# Fish_Feeder_Schematic_Version_2.net
KiCad netlist of a schematic drawn in Altium Designer
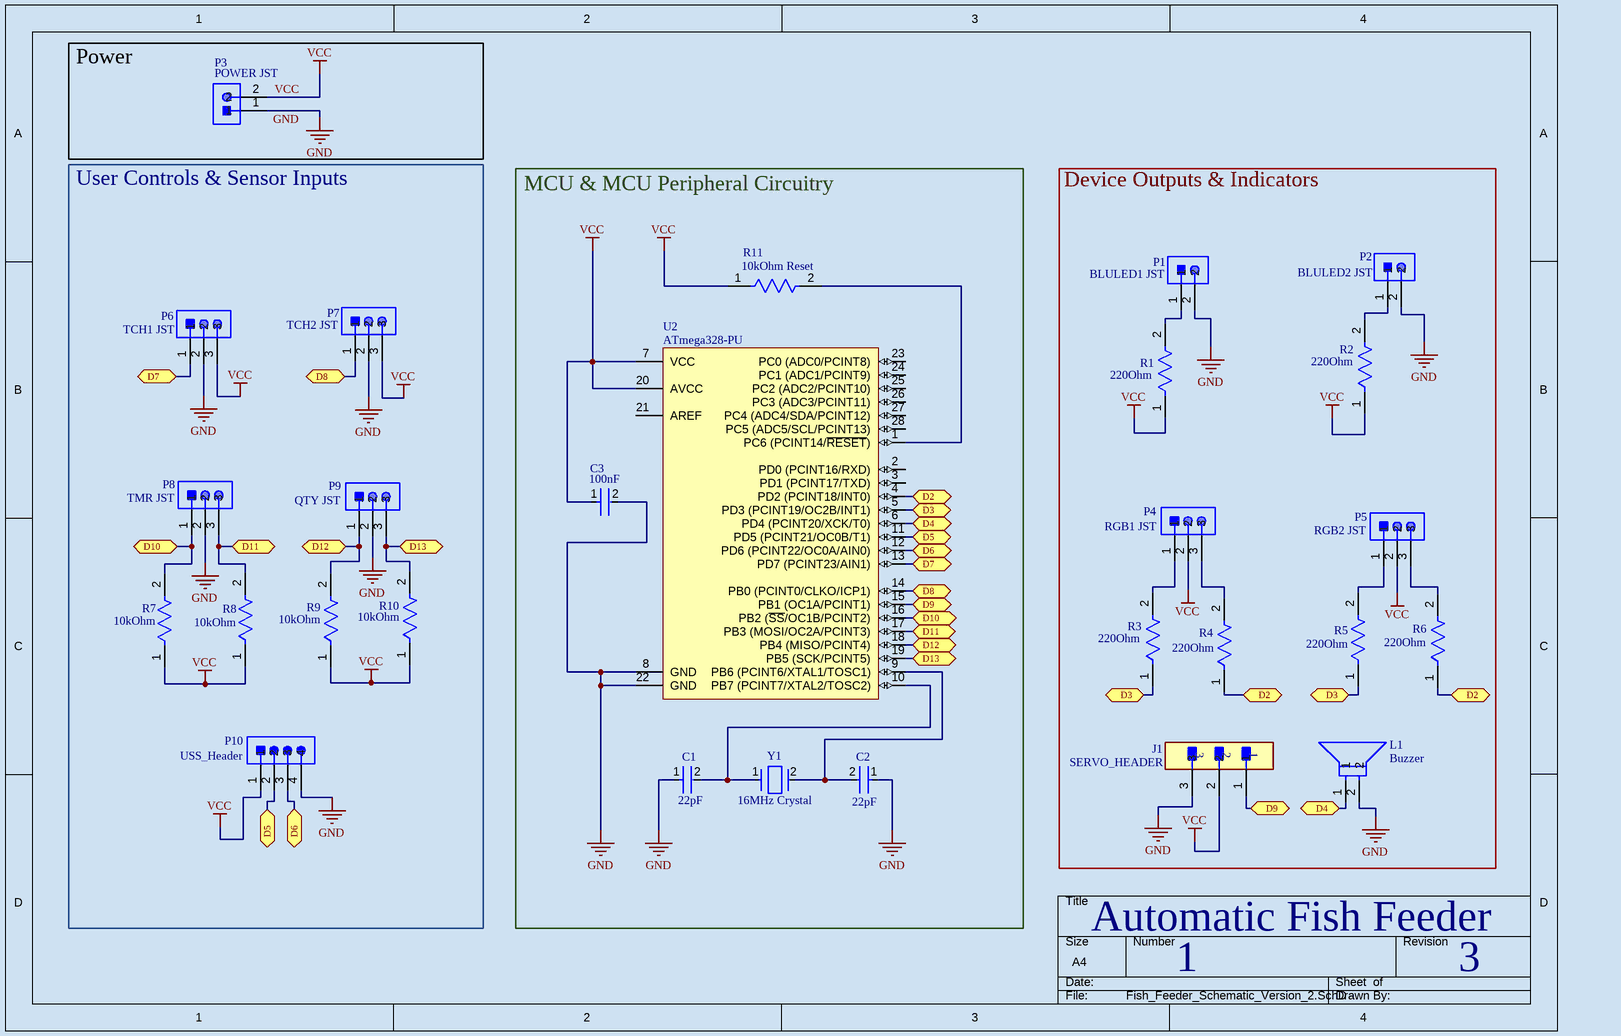
[diagram p0: Fish_Feeder_Schematic_Version_2.SchDoc]

(export (version "E")
  (design (tool "Eeschema 10.0.6"))
  (components
    (comp (ref "C1")
      (value "22pF")
      (footprint "FP-VY1470-MFG")
      (description "CAP CER 2200PF 760VAC Y5U RADIAL")
      (fields (field (name "VOLTAGE") "500V") (field (name "TOLERANCE") "20%"))
      (libsource (lib "Altium Content Vault") (part "11868f565c42a9108669ba33697ecf6"))
    )
    (comp (ref "C2")
      (value "22pF")
      (footprint "FP-VY1470-MFG")
      (description "CAP CER 2200PF 760VAC Y5U RADIAL")
      (fields (field (name "VOLTAGE") "500V") (field (name "TOLERANCE") "20%"))
      (libsource (lib "Altium Content Vault") (part "11868f565c42a9108669ba33697ecf6"))
    )
    (comp (ref "C3")
      (value "100nF")
      (footprint "FP-VY1470-MFG")
      (description "CAP CER 2200PF 760VAC Y5U RADIAL")
      (fields (field (name "VOLTAGE") "500V") (field (name "TOLERANCE") "20%"))
      (libsource (lib "Altium Content Vault") (part "11868f565c42a9108669ba33697ecf6"))
    )
    (comp (ref "J1")
      (value "SERVO_HEADER")
      (footprint "FP-87224-3-MFG")
      (description "CONN HEADER VERT 3POS 2.54MM")
      (libsource (lib "Altium Content Vault") (part "0d3f023dd272f625e17a2be33dea85f"))
    )
    (comp (ref "L1")
      (value "Buzzer")
      (footprint "FP-PS1440P02BT-MFG")
      (description "AUDIO PIEZO TRANSDUCER 30V TH")
      (libsource (lib "Altium Content Vault") (part "5f581d31613f872430949aa526fd155"))
    )
    (comp (ref "P1")
      (value "BLULED1 JST")
      (footprint "JST-S2B-PH-K-S_V")
      (fields (field (name "TOLERANCE") "20%"))
      (libsource (lib "Altium Content Vault") (part "CN-1P-M-R2"))
    )
    (comp (ref "P2")
      (value "BLULED2 JST")
      (footprint "JST-S2B-PH-K-S_V")
      (fields (field (name "TOLERANCE") "20%"))
      (libsource (lib "Altium Content Vault") (part "CN-1P-M-R2"))
    )
    (comp (ref "P3")
      (value "POWER JST")
      (footprint "JST-S2B-PH-K-S_V")
      (fields (field (name "TOLERANCE") "20%"))
      (libsource (lib "") (part "CN-1P-M-R2_1"))
    )
    (comp (ref "P4")
      (value "RGB1 JST")
      (footprint "JST-B3B-PH-K-S-3_V")
      (fields (field (name "MANUFACTURER") "JST"))
      (libsource (lib "Altium Content Vault") (part "CN-1P-M-R3"))
    )
    (comp (ref "P5")
      (value "RGB2 JST")
      (footprint "JST-B3B-PH-K-S-3_V")
      (fields (field (name "MANUFACTURER") "JST"))
      (libsource (lib "Altium Content Vault") (part "CN-1P-M-R3"))
    )
    (comp (ref "P6")
      (value "TCH1 JST")
      (footprint "JST-B3B-PH-K-S-3_V")
      (fields (field (name "MANUFACTURER") "JST"))
      (libsource (lib "Altium Content Vault") (part "CN-1P-M-R3"))
    )
    (comp (ref "P7")
      (value "TCH2 JST")
      (footprint "JST-B3B-PH-K-S-3_V")
      (fields (field (name "MANUFACTURER") "JST"))
      (libsource (lib "Altium Content Vault") (part "CN-1P-M-R3"))
    )
    (comp (ref "P8")
      (value "TMR JST")
      (footprint "JST-B3B-PH-K-S-3_V")
      (fields (field (name "MANUFACTURER") "JST"))
      (libsource (lib "Altium Content Vault") (part "CN-1P-M-R3"))
    )
    (comp (ref "P9")
      (value "QTY JST")
      (footprint "JST-B3B-PH-K-S-3_V")
      (fields (field (name "MANUFACTURER") "JST"))
      (libsource (lib "Altium Content Vault") (part "CN-1P-M-R3"))
    )
    (comp (ref "P10")
      (value "USS_Header")
      (footprint "TECO-640456-4")
      (description "Male Header, Pitch 2.54 mm, 1 x 4 Position, Height 10.03 mm, Tail Length 3.56 mm, RoHS, Bulk")
      (fields (field (name "MANUFACTURER") "TE Connectivity"))
      (libsource (lib "Altium Content Vault") (part "CN-1P-M-R4"))
    )
    (comp (ref "R1")
      (value "220Ohm")
      (footprint "FP-CFR-25-MFG")
      (description "RES 10 OHM 1/4W 5% AXIAL")
      (fields (field (name "TOLERANCE") "5%"))
      (libsource (lib "Altium Content Vault") (part "1029c3af85768c4190bb7ad29bc67b5"))
    )
    (comp (ref "R2")
      (value "220Ohm")
      (footprint "FP-CFR-25-MFG")
      (description "RES 10 OHM 1/4W 5% AXIAL")
      (fields (field (name "TOLERANCE") "5%"))
      (libsource (lib "Altium Content Vault") (part "1029c3af85768c4190bb7ad29bc67b5"))
    )
    (comp (ref "R3")
      (value "220Ohm")
      (footprint "FP-CFR-25-MFG")
      (description "RES 10 OHM 1/4W 5% AXIAL")
      (fields (field (name "TOLERANCE") "5%"))
      (libsource (lib "Altium Content Vault") (part "1029c3af85768c4190bb7ad29bc67b5"))
    )
    (comp (ref "R4")
      (value "220Ohm")
      (footprint "FP-CFR-25-MFG")
      (description "RES 10 OHM 1/4W 5% AXIAL")
      (fields (field (name "TOLERANCE") "5%"))
      (libsource (lib "Altium Content Vault") (part "1029c3af85768c4190bb7ad29bc67b5"))
    )
    (comp (ref "R5")
      (value "220Ohm")
      (footprint "FP-CFR-25-MFG")
      (description "RES 10 OHM 1/4W 5% AXIAL")
      (fields (field (name "TOLERANCE") "5%"))
      (libsource (lib "Altium Content Vault") (part "1029c3af85768c4190bb7ad29bc67b5"))
    )
    (comp (ref "R6")
      (value "220Ohm")
      (footprint "FP-CFR-25-MFG")
      (description "RES 10 OHM 1/4W 5% AXIAL")
      (fields (field (name "TOLERANCE") "5%"))
      (libsource (lib "Altium Content Vault") (part "1029c3af85768c4190bb7ad29bc67b5"))
    )
    (comp (ref "R7")
      (value "10kOhm")
      (footprint "FP-CFR-25-MFG")
      (description "RES 10 OHM 1/4W 5% AXIAL")
      (fields (field (name "TOLERANCE") "5%"))
      (libsource (lib "Altium Content Vault") (part "1029c3af85768c4190bb7ad29bc67b5"))
    )
    (comp (ref "R8")
      (value "10kOhm")
      (footprint "FP-CFR-25-MFG")
      (description "RES 10 OHM 1/4W 5% AXIAL")
      (fields (field (name "TOLERANCE") "5%"))
      (libsource (lib "Altium Content Vault") (part "1029c3af85768c4190bb7ad29bc67b5"))
    )
    (comp (ref "R9")
      (value "10kOhm")
      (footprint "FP-CFR-25-MFG")
      (description "RES 10 OHM 1/4W 5% AXIAL")
      (fields (field (name "TOLERANCE") "5%"))
      (libsource (lib "Altium Content Vault") (part "1029c3af85768c4190bb7ad29bc67b5"))
    )
    (comp (ref "R10")
      (value "10kOhm")
      (footprint "FP-CFR-25-MFG")
      (description "RES 10 OHM 1/4W 5% AXIAL")
      (fields (field (name "TOLERANCE") "5%"))
      (libsource (lib "Altium Content Vault") (part "1029c3af85768c4190bb7ad29bc67b5"))
    )
    (comp (ref "R11")
      (value "10kOhm Reset")
      (footprint "FP-CFR-25-MFG")
      (description "RES 10 OHM 1/4W 5% AXIAL")
      (fields (field (name "TOLERANCE") "5%"))
      (libsource (lib "Altium Content Vault") (part "1029c3af85768c4190bb7ad29bc67b5"))
    )
    (comp (ref "U2")
      (value "ATmega328-PU")
      (footprint "28P3")
      (libsource (lib "Altium Content Vault") (part "MC-8B-ATM48-IL28"))
    )
    (comp (ref "Y1")
      (value "16MHz Crystal")
      (footprint "FP-ABL-MFG")
      (description "CRYSTAL 16.0000MHZ 18PF TH")
      (fields (field (name "TOLERANCE") "30ppm"))
      (libsource (lib "Altium Content Vault") (part "c23a69dc6c9e2f18f2079038eb95dd1"))
    )
  )
  (nets
    (net (code "1") (name "/D2") (class "Default")
      (node (ref "R4") (pin "1") (pinfunction "1_1") (pintype "passive"))
      (node (ref "R6") (pin "1") (pinfunction "1_1") (pintype "passive"))
      (node (ref "U2") (pin "4") (pinfunction "PD2_(PCINT18/INT0)_4") (pintype "bidirectional"))
    )
    (net (code "2") (name "/D3") (class "Default")
      (node (ref "R3") (pin "1") (pinfunction "1_1") (pintype "passive"))
      (node (ref "R5") (pin "1") (pinfunction "1_1") (pintype "passive"))
      (node (ref "U2") (pin "5") (pinfunction "PD3_(PCINT19/OC2B/INT1)_5") (pintype "bidirectional"))
    )
    (net (code "3") (name "/D4") (class "Default")
      (node (ref "L1") (pin "1") (pinfunction "1_1") (pintype "passive"))
      (node (ref "U2") (pin "6") (pinfunction "PD4_(PCINT20/XCK/T0)_6") (pintype "bidirectional"))
    )
    (net (code "4") (name "/D5") (class "Default")
      (node (ref "P10") (pin "2") (pinfunction "2_2") (pintype "passive"))
      (node (ref "U2") (pin "11") (pinfunction "PD5_(PCINT21/OC0B/T1)_11") (pintype "bidirectional"))
    )
    (net (code "5") (name "/D6") (class "Default")
      (node (ref "P10") (pin "3") (pinfunction "3_3") (pintype "passive"))
      (node (ref "U2") (pin "12") (pinfunction "PD6_(PCINT22/OC0A/AIN0)_12") (pintype "bidirectional"))
    )
    (net (code "6") (name "/D7") (class "Default")
      (node (ref "P6") (pin "1") (pinfunction "1_1") (pintype "passive"))
      (node (ref "U2") (pin "13") (pinfunction "PD7_(PCINT23/AIN1)_13") (pintype "bidirectional"))
    )
    (net (code "7") (name "/D8") (class "Default")
      (node (ref "P7") (pin "1") (pinfunction "1_1") (pintype "passive"))
      (node (ref "U2") (pin "14") (pinfunction "PB0_(PCINT0/CLKO/ICP1)_14") (pintype "bidirectional"))
    )
    (net (code "8") (name "/D9") (class "Default")
      (node (ref "J1") (pin "1") (pinfunction "1_1") (pintype "passive"))
      (node (ref "U2") (pin "15") (pinfunction "PB1_(OC1A/PCINT1)_15") (pintype "bidirectional"))
    )
    (net (code "9") (name "/D10") (class "Default")
      (node (ref "P8") (pin "1") (pinfunction "1_1") (pintype "passive"))
      (node (ref "R7") (pin "2") (pinfunction "2_2") (pintype "passive"))
      (node (ref "U2") (pin "16") (pinfunction "PB2_(~{SS}/OC1B/PCINT2)_16") (pintype "bidirectional"))
    )
    (net (code "10") (name "/D11") (class "Default")
      (node (ref "P8") (pin "3") (pinfunction "3_3") (pintype "passive"))
      (node (ref "R8") (pin "2") (pinfunction "2_2") (pintype "passive"))
      (node (ref "U2") (pin "17") (pinfunction "PB3_(MOSI/OC2A/PCINT3)_17") (pintype "bidirectional"))
    )
    (net (code "11") (name "/D12") (class "Default")
      (node (ref "P9") (pin "1") (pinfunction "1_1") (pintype "passive"))
      (node (ref "R9") (pin "2") (pinfunction "2_2") (pintype "passive"))
      (node (ref "U2") (pin "18") (pinfunction "PB4_(MISO/PCINT4)_18") (pintype "bidirectional"))
    )
    (net (code "12") (name "/D13") (class "Default")
      (node (ref "P9") (pin "3") (pinfunction "3_3") (pintype "passive"))
      (node (ref "R10") (pin "2") (pinfunction "2_2") (pintype "passive"))
      (node (ref "U2") (pin "19") (pinfunction "PB5_(SCK/PCINT5)_19") (pintype "bidirectional"))
    )
    (net (code "13") (name "GND") (class "Default")
      (node (ref "C1") (pin "1") (pinfunction "1_1") (pintype "passive"))
      (node (ref "C2") (pin "1") (pinfunction "1_1") (pintype "passive"))
      (node (ref "C3") (pin "2") (pinfunction "2_2") (pintype "passive"))
      (node (ref "J1") (pin "3") (pinfunction "3_3") (pintype "passive"))
      (node (ref "L1") (pin "2") (pinfunction "2_2") (pintype "passive"))
      (node (ref "P1") (pin "2") (pinfunction "2_2") (pintype "passive"))
      (node (ref "P10") (pin "4") (pinfunction "4_4") (pintype "passive"))
      (node (ref "P2") (pin "2") (pinfunction "2_2") (pintype "passive"))
      (node (ref "P3") (pin "1") (pinfunction "1_1") (pintype "passive"))
      (node (ref "P6") (pin "2") (pinfunction "2_2") (pintype "passive"))
      (node (ref "P7") (pin "2") (pinfunction "2_2") (pintype "passive"))
      (node (ref "P8") (pin "2") (pinfunction "2_2") (pintype "passive"))
      (node (ref "P9") (pin "2") (pinfunction "2_2") (pintype "passive"))
      (node (ref "U2") (pin "22") (pinfunction "GND_22") (pintype "power_in"))
      (node (ref "U2") (pin "8") (pinfunction "GND_8") (pintype "power_in"))
    )
    (net (code "14") (name "Net-(P1-Pad1)") (class "Default")
      (node (ref "P1") (pin "1") (pinfunction "1_1") (pintype "passive"))
      (node (ref "R1") (pin "2") (pinfunction "2_2") (pintype "passive"))
    )
    (net (code "15") (name "Net-(P2-Pad1)") (class "Default")
      (node (ref "P2") (pin "1") (pinfunction "1_1") (pintype "passive"))
      (node (ref "R2") (pin "2") (pinfunction "2_2") (pintype "passive"))
    )
    (net (code "16") (name "Net-(P4-Pad1)") (class "Default")
      (node (ref "P4") (pin "1") (pinfunction "1_1") (pintype "passive"))
      (node (ref "R3") (pin "2") (pinfunction "2_2") (pintype "passive"))
    )
    (net (code "17") (name "Net-(P4-Pad3)") (class "Default")
      (node (ref "P4") (pin "3") (pinfunction "3_3") (pintype "passive"))
      (node (ref "R4") (pin "2") (pinfunction "2_2") (pintype "passive"))
    )
    (net (code "18") (name "Net-(P5-Pad1)") (class "Default")
      (node (ref "P5") (pin "1") (pinfunction "1_1") (pintype "passive"))
      (node (ref "R5") (pin "2") (pinfunction "2_2") (pintype "passive"))
    )
    (net (code "19") (name "Net-(P5-Pad3)") (class "Default")
      (node (ref "P5") (pin "3") (pinfunction "3_3") (pintype "passive"))
      (node (ref "R6") (pin "2") (pinfunction "2_2") (pintype "passive"))
    )
    (net (code "20") (name "Net-(U2-PB6_(PCINT6{slash}XTAL1{slash}TOSC1))") (class "Default")
      (node (ref "C2") (pin "2") (pinfunction "2_2") (pintype "passive"))
      (node (ref "U2") (pin "9") (pinfunction "PB6_(PCINT6/XTAL1/TOSC1)_9") (pintype "bidirectional"))
      (node (ref "Y1") (pin "2") (pinfunction "2_2") (pintype "passive"))
    )
    (net (code "21") (name "Net-(U2-PB7_(PCINT7{slash}XTAL2{slash}TOSC2))") (class "Default")
      (node (ref "C1") (pin "2") (pinfunction "2_2") (pintype "passive"))
      (node (ref "U2") (pin "10") (pinfunction "PB7_(PCINT7/XTAL2/TOSC2)_10") (pintype "bidirectional"))
      (node (ref "Y1") (pin "1") (pinfunction "1_1") (pintype "passive"))
    )
    (net (code "22") (name "Net-(U2-PC6_(PCINT14{slash}~{RESET}))") (class "Default")
      (node (ref "R11") (pin "2") (pinfunction "2_2") (pintype "passive"))
      (node (ref "U2") (pin "1") (pinfunction "PC6_(PCINT14/~{RESET})_1") (pintype "bidirectional"))
    )
    (net (code "23") (name "VCC") (class "Default")
      (node (ref "C3") (pin "1") (pinfunction "1_1") (pintype "passive"))
      (node (ref "J1") (pin "2") (pinfunction "2_2") (pintype "passive"))
      (node (ref "P10") (pin "1") (pinfunction "1_1") (pintype "passive"))
      (node (ref "P3") (pin "2") (pinfunction "2_2") (pintype "passive"))
      (node (ref "P4") (pin "2") (pinfunction "2_2") (pintype "passive"))
      (node (ref "P5") (pin "2") (pinfunction "2_2") (pintype "passive"))
      (node (ref "P6") (pin "3") (pinfunction "3_3") (pintype "passive"))
      (node (ref "P7") (pin "3") (pinfunction "3_3") (pintype "passive"))
      (node (ref "R1") (pin "1") (pinfunction "1_1") (pintype "passive"))
      (node (ref "R10") (pin "1") (pinfunction "1_1") (pintype "passive"))
      (node (ref "R11") (pin "1") (pinfunction "1_1") (pintype "passive"))
      (node (ref "R2") (pin "1") (pinfunction "1_1") (pintype "passive"))
      (node (ref "R7") (pin "1") (pinfunction "1_1") (pintype "passive"))
      (node (ref "R8") (pin "1") (pinfunction "1_1") (pintype "passive"))
      (node (ref "R9") (pin "1") (pinfunction "1_1") (pintype "passive"))
      (node (ref "U2") (pin "20") (pinfunction "AVCC_20") (pintype "power_in"))
      (node (ref "U2") (pin "7") (pinfunction "VCC_7") (pintype "power_in"))
    )
    (net (code "24") (name "unconnected-(U2-AREF-Pad21)") (class "Default")
      (node (ref "U2") (pin "21") (pinfunction "AREF_21") (pintype "power_in"))
    )
    (net (code "25") (name "unconnected-(U2-PC0_(ADC0{slash}PCINT8)-Pad23)") (class "Default")
      (node (ref "U2") (pin "23") (pinfunction "PC0_(ADC0/PCINT8)_23") (pintype "bidirectional"))
    )
    (net (code "26") (name "unconnected-(U2-PC1_(ADC1{slash}PCINT9)-Pad24)") (class "Default")
      (node (ref "U2") (pin "24") (pinfunction "PC1_(ADC1/PCINT9)_24") (pintype "bidirectional"))
    )
    (net (code "27") (name "unconnected-(U2-PC2_(ADC2{slash}PCINT10)-Pad25)") (class "Default")
      (node (ref "U2") (pin "25") (pinfunction "PC2_(ADC2/PCINT10)_25") (pintype "bidirectional"))
    )
    (net (code "28") (name "unconnected-(U2-PC3_(ADC3{slash}PCINT11)-Pad26)") (class "Default")
      (node (ref "U2") (pin "26") (pinfunction "PC3_(ADC3/PCINT11)_26") (pintype "bidirectional"))
    )
    (net (code "29") (name "unconnected-(U2-PC4_(ADC4{slash}SDA{slash}PCINT12)-Pad27)") (class "Default")
      (node (ref "U2") (pin "27") (pinfunction "PC4_(ADC4/SDA/PCINT12)_27") (pintype "bidirectional"))
    )
    (net (code "30") (name "unconnected-(U2-PC5_(ADC5{slash}SCL{slash}PCINT13)-Pad28)") (class "Default")
      (node (ref "U2") (pin "28") (pinfunction "PC5_(ADC5/SCL/PCINT13)_28") (pintype "bidirectional"))
    )
    (net (code "31") (name "unconnected-(U2-PD0_(PCINT16{slash}RXD)-Pad2)") (class "Default")
      (node (ref "U2") (pin "2") (pinfunction "PD0_(PCINT16/RXD)_2") (pintype "bidirectional"))
    )
    (net (code "32") (name "unconnected-(U2-PD1_(PCINT17{slash}TXD)-Pad3)") (class "Default")
      (node (ref "U2") (pin "3") (pinfunction "PD1_(PCINT17/TXD)_3") (pintype "bidirectional"))
    )
  )
)
